# Waveshape_LFO_v1_Main.net
KiCad netlist of a schematic drawn in Altium Designer
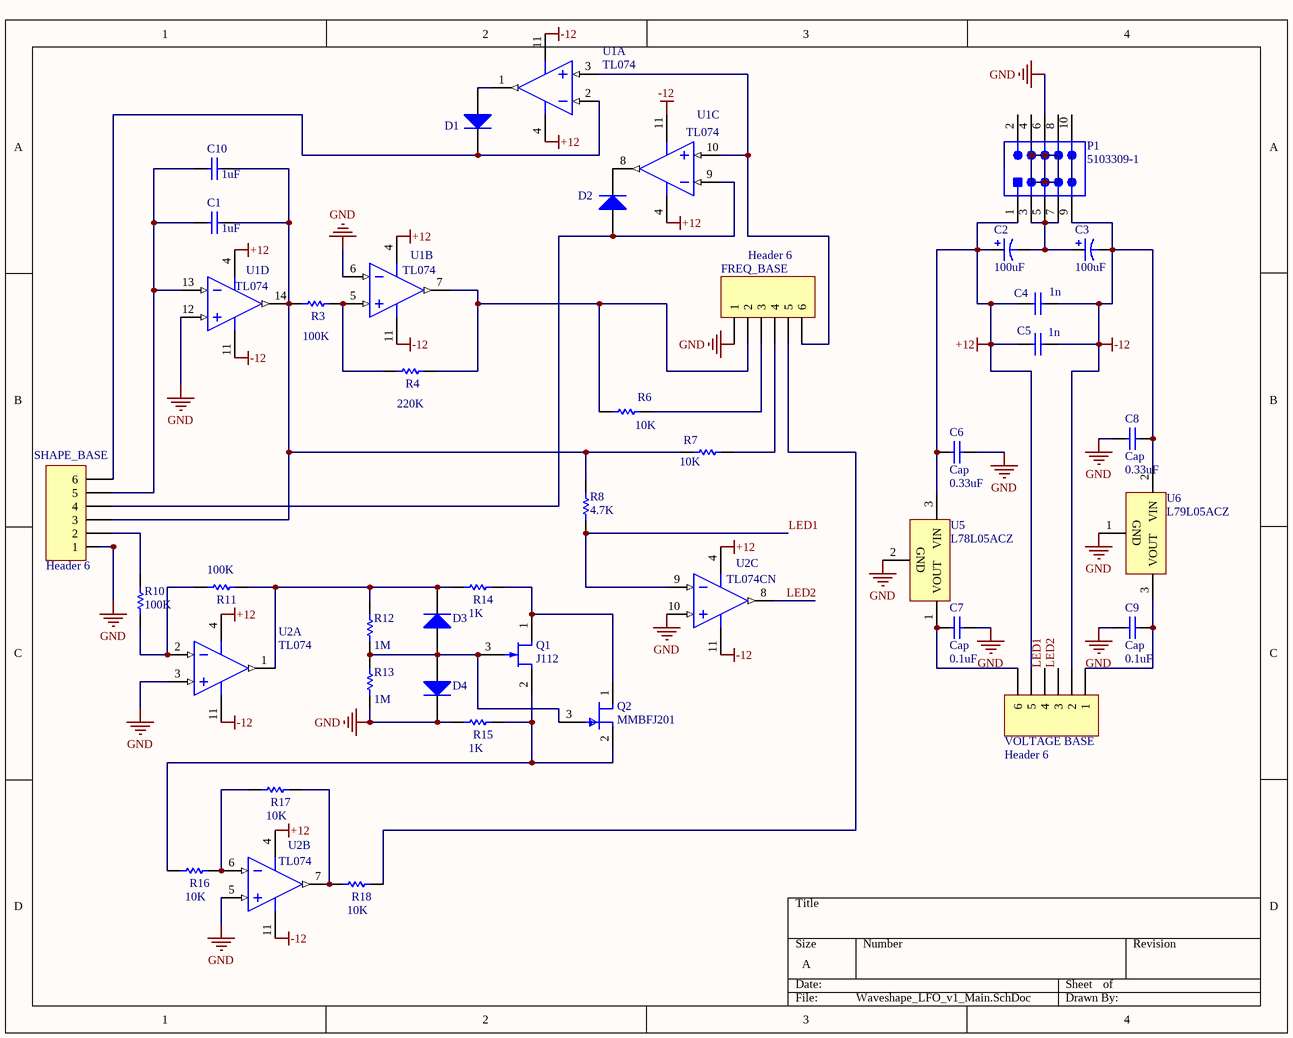
[diagram p0: Waveshape_LFO_v1_Main.SchDoc]

(export (version "E")
  (design (tool "Eeschema 10.0.6"))
  (components
    (comp (ref "C1")
      (value "1uF")
      (footprint "RAD-0.1")
      (description "Capacitor")
      (fields (field (name "Comment") "Cap") (field (name "PUBLISHER") "Altium Limited"))
      (libsource (lib "Miscellaneous Devices") (part "Cap"))
    )
    (comp (ref "C2")
      (value "100uF")
      (footprint "CAPR5-4X5")
      (description "Polarized Capacitor (Radial)")
      (fields (field (name "Comment") "Cap Pol1") (field (name "PUBLISHER") "Altium Limited"))
      (libsource (lib "Miscellaneous Devices") (part "Cap Pol1"))
    )
    (comp (ref "C3")
      (value "100uF")
      (footprint "CAPR5-4X5")
      (description "Polarized Capacitor (Radial)")
      (fields (field (name "Comment") "Cap Pol1") (field (name "PUBLISHER") "Altium Limited"))
      (libsource (lib "Miscellaneous Devices") (part "Cap Pol1"))
    )
    (comp (ref "C4")
      (value "1n")
      (footprint "RAD-0.1")
      (description "Capacitor")
      (fields (field (name "Comment") "Cap") (field (name "PUBLISHER") "Altium Limited"))
      (libsource (lib "Miscellaneous Devices") (part "Cap"))
    )
    (comp (ref "C5")
      (value "1n")
      (footprint "RAD-0.1")
      (description "Capacitor")
      (fields (field (name "Comment") "Cap") (field (name "PUBLISHER") "Altium Limited"))
      (libsource (lib "Miscellaneous Devices") (part "Cap"))
    )
    (comp (ref "C6")
      (value "Cap")
      (footprint "RAD-0.3")
      (description "Capacitor")
      (fields (field (name "ALTIUM_VALUE") "0.33uF") (field (name "PUBLISHER") "Altium Limited"))
      (libsource (lib "Miscellaneous Devices") (part "Cap"))
    )
    (comp (ref "C7")
      (value "Cap")
      (footprint "RAD-0.3")
      (description "Capacitor")
      (fields (field (name "ALTIUM_VALUE") "0.1uF") (field (name "PUBLISHER") "Altium Limited"))
      (libsource (lib "Miscellaneous Devices") (part "Cap"))
    )
    (comp (ref "C8")
      (value "Cap")
      (footprint "RAD-0.3")
      (description "Capacitor")
      (fields (field (name "ALTIUM_VALUE") "0.33uF") (field (name "PUBLISHER") "Altium Limited"))
      (libsource (lib "Miscellaneous Devices") (part "Cap"))
    )
    (comp (ref "C9")
      (value "Cap")
      (footprint "RAD-0.3")
      (description "Capacitor")
      (fields (field (name "ALTIUM_VALUE") "0.1uF") (field (name "PUBLISHER") "Altium Limited"))
      (libsource (lib "Miscellaneous Devices") (part "Cap"))
    )
    (comp (ref "C10")
      (value "1uF")
      (footprint "RAD-0.1")
      (description "Capacitor")
      (fields (field (name "Comment") "Cap") (field (name "PUBLISHER") "Altium Limited"))
      (libsource (lib "Miscellaneous Devices") (part "Cap"))
    )
    (comp (ref "D1")
      (value "Diode 1N4148")
      (footprint "DO-35")
      (description "High Conductance Fast Diode")
      (fields (field (name "PUBLISHER") "Altium Limited"))
      (libsource (lib "Miscellaneous Devices") (part "Diode 1N4148"))
    )
    (comp (ref "D2")
      (value "Diode 1N4148")
      (footprint "DO-35")
      (description "High Conductance Fast Diode")
      (fields (field (name "PUBLISHER") "Altium Limited"))
      (libsource (lib "Miscellaneous Devices") (part "Diode 1N4148"))
    )
    (comp (ref "D3")
      (value "1N4148")
      (footprint "DO-35")
      (description "High Conductance Fast Diode")
      (fields (field (name "PUBLISHER") "Altium Limited"))
      (libsource (lib "Miscellaneous Devices") (part "Diode 1N4148"))
    )
    (comp (ref "D4")
      (value "Diode 1N4148")
      (footprint "DO-35")
      (description "High Conductance Fast Diode")
      (fields (field (name "PUBLISHER") "Altium Limited"))
      (libsource (lib "Miscellaneous Devices") (part "Diode 1N4148"))
    )
    (comp (ref "FREQ_BASE")
      (value "Header 6")
      (footprint "HDR1X6")
      (description "Header, 6-Pin")
      (fields (field (name "PUBLISHER") "Altium Limited"))
      (libsource (lib "") (part "Header 6_1"))
    )
    (comp (ref "P1")
      (value "5103309-1")
      (footprint "TECO-5103309-1_V")
      (fields (field (name "MANUFACTURER") "TE Connectivity"))
      (libsource (lib "Altium Content Vault") (part "CN-2P-M-R10"))
    )
    (comp (ref "Q1")
      (value "J112")
      (footprint "ONSC-TO-92-3-29-11")
      (description "JFET Chopper Transistor, N-Channel - Depletion, 3-Pin TO-92, Bulk Box")
      (fields (field (name "MANUFACTURER") "On Semiconductor"))
      (libsource (lib "Altium Content Vault") (part "ONSC-JFET-D1S2G3-3-B"))
    )
    (comp (ref "Q2")
      (value "MMBFJ201")
      (footprint "FP-318BM-IPC_C")
      (description "JFET N-Channel 40V  350mW Surface Mount SOT-23-3")
      (fields (field (name "MANUFACTURER") "ON Semiconductor"))
      (libsource (lib "Altium Content Vault") (part "14398f7355be6f33287877db3ee21c7"))
    )
    (comp (ref "R3")
      (value "100K")
      (footprint "AXIAL-0.3")
      (description "Resistor")
      (fields (field (name "PUBLISHER") "Altium Limited"))
      (libsource (lib "Miscellaneous Devices") (part "Res1"))
    )
    (comp (ref "R4")
      (value "220K")
      (footprint "AXIAL-0.3")
      (description "Resistor")
      (fields (field (name "PUBLISHER") "Altium Limited"))
      (libsource (lib "Miscellaneous Devices") (part "Res1"))
    )
    (comp (ref "R6")
      (value "10K")
      (footprint "AXIAL-0.3")
      (description "Resistor")
      (fields (field (name "PUBLISHER") "Altium Limited"))
      (libsource (lib "Miscellaneous Devices") (part "Res1"))
    )
    (comp (ref "R7")
      (value "10K")
      (footprint "AXIAL-0.3")
      (description "Resistor")
      (fields (field (name "PUBLISHER") "Altium Limited"))
      (libsource (lib "Miscellaneous Devices") (part "Res1"))
    )
    (comp (ref "R8")
      (value "4.7K")
      (footprint "AXIAL-0.3")
      (description "Resistor")
      (fields (field (name "PUBLISHER") "Altium Limited"))
      (libsource (lib "Miscellaneous Devices") (part "Res1"))
    )
    (comp (ref "R10")
      (value "100K")
      (footprint "AXIAL-0.3")
      (description "Resistor")
      (fields (field (name "PUBLISHER") "Altium Limited"))
      (libsource (lib "Miscellaneous Devices") (part "Res1"))
    )
    (comp (ref "R11")
      (value "100K")
      (footprint "AXIAL-0.3")
      (description "Resistor")
      (fields (field (name "PUBLISHER") "Altium Limited"))
      (libsource (lib "Miscellaneous Devices") (part "Res1"))
    )
    (comp (ref "R12")
      (value "1M")
      (footprint "AXIAL-0.3")
      (description "Resistor")
      (fields (field (name "PUBLISHER") "Altium Limited"))
      (libsource (lib "Miscellaneous Devices") (part "Res1"))
    )
    (comp (ref "R13")
      (value "1M")
      (footprint "AXIAL-0.3")
      (description "Resistor")
      (fields (field (name "PUBLISHER") "Altium Limited"))
      (libsource (lib "Miscellaneous Devices") (part "Res1"))
    )
    (comp (ref "R14")
      (value "1K")
      (footprint "AXIAL-0.3")
      (description "Resistor")
      (fields (field (name "PUBLISHER") "Altium Limited"))
      (libsource (lib "Miscellaneous Devices") (part "Res1"))
    )
    (comp (ref "R15")
      (value "1K")
      (footprint "AXIAL-0.3")
      (description "Resistor")
      (fields (field (name "PUBLISHER") "Altium Limited"))
      (libsource (lib "Miscellaneous Devices") (part "Res1"))
    )
    (comp (ref "R16")
      (value "10K")
      (footprint "AXIAL-0.3")
      (description "Resistor")
      (fields (field (name "PUBLISHER") "Altium Limited"))
      (libsource (lib "Miscellaneous Devices") (part "Res1"))
    )
    (comp (ref "R17")
      (value "10K")
      (footprint "AXIAL-0.3")
      (description "Resistor")
      (fields (field (name "PUBLISHER") "Altium Limited"))
      (libsource (lib "Miscellaneous Devices") (part "Res1"))
    )
    (comp (ref "R18")
      (value "10K")
      (footprint "AXIAL-0.3")
      (description "Resistor")
      (fields (field (name "PUBLISHER") "Altium Limited"))
      (libsource (lib "Miscellaneous Devices") (part "Res1"))
    )
    (comp (ref "SHAPE_BASE")
      (value "Header 6")
      (footprint "HDR1X6")
      (description "Header, 6-Pin")
      (fields (field (name "PUBLISHER") "Altium Limited"))
      (libsource (lib "") (part "Header 6_2"))
    )
    (comp (ref "U1")
      (value "TL074")
      (footprint "N0014A")
      (fields (field (name "MANUFACTURER") "Texas Instruments") (field (name "PARTNUMBER") "TL074CN"))
      (libsource (lib "Altium Content Vault") (part "TI-TLXX4X_MC3403-X14"))
    )
    (comp (ref "U2")
      (value "TL074CN")
      (footprint "N0014A")
      (fields (field (name "MANUFACTURER") "Texas Instruments") (field (name "PARTNUMBER") "TL074CN"))
      (libsource (lib "Altium Content Vault") (part "TI-TLXX4X_MC3403-X14"))
    )
    (comp (ref "U5")
      (value "L78L05ACZ")
      (footprint "TO-92")
      (description "Positive Voltage Regulator, 5V, 3-Pin TO-92")
      (libsource (lib "Altium Content Vault") (part "PM-REG-7805-SIL3"))
    )
    (comp (ref "U6")
      (value "L79L05ACZ")
      (footprint "TO-92")
      (description "Negative Voltage Regulator, -5V, 3-Pin TO-92")
      (libsource (lib "Altium Content Vault") (part "PM-REG-7905-SIL3A"))
    )
    (comp (ref "VOLTAGE BASE")
      (value "Header 6")
      (footprint "HDR1X6")
      (description "Header, 6-Pin")
      (fields (field (name "PUBLISHER") "Altium Limited"))
      (libsource (lib "Miscellaneous Connectors") (part "Header 6"))
    )
  )
  (nets
    (net (code "1") (name "+12") (class "Default")
      (node (ref "C2") (pin "1") (pinfunction "1_1") (pintype "passive"))
      (node (ref "C4") (pin "1") (pinfunction "1_1") (pintype "passive"))
      (node (ref "C5") (pin "1") (pinfunction "1_1") (pintype "passive"))
      (node (ref "C6") (pin "1") (pinfunction "1_1") (pintype "passive"))
      (node (ref "P1") (pin "1") (pinfunction "1_1") (pintype "passive"))
      (node (ref "U1") (pin "4") (pinfunction "VCC+_4") (pintype "power_in"))
      (node (ref "U2") (pin "4") (pinfunction "VCC+_4") (pintype "power_in"))
      (node (ref "U5") (pin "3") (pinfunction "VIN_3") (pintype "power_in"))
      (node (ref "VOLTAGE BASE") (pin "5") (pinfunction "5_5") (pintype "passive"))
    )
    (net (code "2") (name "-12") (class "Default")
      (node (ref "C3") (pin "2") (pinfunction "2_2") (pintype "passive"))
      (node (ref "C4") (pin "2") (pinfunction "2_2") (pintype "passive"))
      (node (ref "C5") (pin "2") (pinfunction "2_2") (pintype "passive"))
      (node (ref "C8") (pin "2") (pinfunction "2_2") (pintype "passive"))
      (node (ref "P1") (pin "9") (pinfunction "9_9") (pintype "passive"))
      (node (ref "U1") (pin "11") (pinfunction "VCC-_11") (pintype "power_in"))
      (node (ref "U2") (pin "11") (pinfunction "VCC-_11") (pintype "power_in"))
      (node (ref "U6") (pin "2") (pinfunction "VIN_2") (pintype "power_in"))
      (node (ref "VOLTAGE BASE") (pin "2") (pinfunction "2_2") (pintype "passive"))
    )
    (net (code "3") (name "/LED1") (class "Default")
      (node (ref "R8") (pin "1") (pinfunction "1_1") (pintype "passive"))
      (node (ref "U2") (pin "9") (pinfunction "IN3-_9") (pintype "input"))
      (node (ref "VOLTAGE BASE") (pin "4") (pinfunction "4_4") (pintype "passive"))
    )
    (net (code "4") (name "/LED2") (class "Default")
      (node (ref "U2") (pin "8") (pinfunction "OUT3_8") (pintype "output"))
      (node (ref "VOLTAGE BASE") (pin "3") (pinfunction "3_3") (pintype "passive"))
    )
    (net (code "5") (name "GND") (class "Default")
      (node (ref "C6") (pin "2") (pinfunction "2_2") (pintype "passive"))
      (node (ref "C7") (pin "2") (pinfunction "2_2") (pintype "passive"))
      (node (ref "C8") (pin "1") (pinfunction "1_1") (pintype "passive"))
      (node (ref "C9") (pin "1") (pinfunction "1_1") (pintype "passive"))
      (node (ref "D4") (pin "2") (pinfunction "K_2") (pintype "passive"))
      (node (ref "FREQ_BASE") (pin "1") (pinfunction "1_1") (pintype "passive"))
      (node (ref "P1") (pin "6") (pinfunction "6_6") (pintype "passive"))
      (node (ref "R13") (pin "1") (pinfunction "1_1") (pintype "passive"))
      (node (ref "R15") (pin "1") (pinfunction "1_1") (pintype "passive"))
      (node (ref "SHAPE_BASE") (pin "1") (pinfunction "1_1") (pintype "passive"))
      (node (ref "U1") (pin "12") (pinfunction "IN4+_12") (pintype "input"))
      (node (ref "U1") (pin "6") (pinfunction "IN2-_6") (pintype "input"))
      (node (ref "U2") (pin "10") (pinfunction "IN3+_10") (pintype "input"))
      (node (ref "U2") (pin "3") (pinfunction "IN1+_3") (pintype "input"))
      (node (ref "U2") (pin "5") (pinfunction "IN2+_5") (pintype "input"))
      (node (ref "U5") (pin "2") (pinfunction "GND_2") (pintype "power_in"))
      (node (ref "U6") (pin "1") (pinfunction "GND_1") (pintype "power_in"))
    )
    (net (code "6") (name "Net-(C2-Pad2)") (class "Default")
      (node (ref "C2") (pin "2") (pinfunction "2_2") (pintype "passive"))
      (node (ref "C3") (pin "1") (pinfunction "1_1") (pintype "passive"))
      (node (ref "P1") (pin "3") (pinfunction "3_3") (pintype "passive"))
      (node (ref "P1") (pin "5") (pinfunction "5_5") (pintype "passive"))
      (node (ref "P1") (pin "7") (pinfunction "7_7") (pintype "passive"))
    )
    (net (code "7") (name "Net-(D1-A)") (class "Default")
      (node (ref "D1") (pin "1") (pinfunction "A_1") (pintype "passive"))
      (node (ref "U1") (pin "1") (pinfunction "OUT1_1") (pintype "output"))
    )
    (net (code "8") (name "Net-(D1-K)") (class "Default")
      (node (ref "D1") (pin "2") (pinfunction "K_2") (pintype "passive"))
      (node (ref "SHAPE_BASE") (pin "6") (pinfunction "6_6") (pintype "passive"))
      (node (ref "U1") (pin "2") (pinfunction "IN1-_2") (pintype "input"))
    )
    (net (code "9") (name "Net-(D2-A)") (class "Default")
      (node (ref "D2") (pin "1") (pinfunction "A_1") (pintype "passive"))
      (node (ref "SHAPE_BASE") (pin "4") (pinfunction "4_4") (pintype "passive"))
      (node (ref "U1") (pin "9") (pinfunction "IN3-_9") (pintype "input"))
    )
    (net (code "10") (name "Net-(D2-K)") (class "Default")
      (node (ref "D2") (pin "2") (pinfunction "K_2") (pintype "passive"))
      (node (ref "U1") (pin "8") (pinfunction "OUT3_8") (pintype "output"))
    )
    (net (code "11") (name "Net-(D3-A)") (class "Default")
      (node (ref "D3") (pin "1") (pinfunction "A_1") (pintype "passive"))
      (node (ref "D4") (pin "1") (pinfunction "A_1") (pintype "passive"))
      (node (ref "Q1") (pin "3") (pinfunction "G_3") (pintype "passive"))
      (node (ref "Q2") (pin "3") (pinfunction "G_3") (pintype "passive"))
      (node (ref "R12") (pin "1") (pinfunction "1_1") (pintype "passive"))
      (node (ref "R13") (pin "2") (pinfunction "2_2") (pintype "passive"))
    )
    (net (code "12") (name "Net-(D3-K)") (class "Default")
      (node (ref "D3") (pin "2") (pinfunction "K_2") (pintype "passive"))
      (node (ref "R11") (pin "2") (pinfunction "2_2") (pintype "passive"))
      (node (ref "R12") (pin "2") (pinfunction "2_2") (pintype "passive"))
      (node (ref "R14") (pin "1") (pinfunction "1_1") (pintype "passive"))
      (node (ref "U2") (pin "1") (pinfunction "OUT1_1") (pintype "output"))
    )
    (net (code "13") (name "Net-(FREQ_BASE-Pad3)") (class "Default")
      (node (ref "FREQ_BASE") (pin "3") (pinfunction "3_3") (pintype "passive"))
      (node (ref "R6") (pin "2") (pinfunction "2_2") (pintype "passive"))
    )
    (net (code "14") (name "Net-(FREQ_BASE-Pad4)") (class "Default")
      (node (ref "FREQ_BASE") (pin "4") (pinfunction "4_4") (pintype "passive"))
      (node (ref "R7") (pin "1") (pinfunction "1_1") (pintype "passive"))
    )
    (net (code "15") (name "Net-(FREQ_BASE-Pad5)") (class "Default")
      (node (ref "FREQ_BASE") (pin "5") (pinfunction "5_5") (pintype "passive"))
      (node (ref "R18") (pin "2") (pinfunction "2_2") (pintype "passive"))
    )
    (net (code "16") (name "Net-(Q1-D)") (class "Default")
      (node (ref "Q1") (pin "1") (pinfunction "D_1") (pintype "passive"))
      (node (ref "Q2") (pin "1") (pinfunction "D_1") (pintype "passive"))
      (node (ref "R14") (pin "2") (pinfunction "2_2") (pintype "passive"))
    )
    (net (code "17") (name "Net-(Q1-S)") (class "Default")
      (node (ref "Q1") (pin "2") (pinfunction "S_2") (pintype "passive"))
      (node (ref "Q2") (pin "2") (pinfunction "S_2") (pintype "passive"))
      (node (ref "R15") (pin "2") (pinfunction "2_2") (pintype "passive"))
      (node (ref "R16") (pin "1") (pinfunction "1_1") (pintype "passive"))
    )
    (net (code "18") (name "Net-(R10-Pad2)") (class "Default")
      (node (ref "R10") (pin "2") (pinfunction "2_2") (pintype "passive"))
      (node (ref "SHAPE_BASE") (pin "2") (pinfunction "2_2") (pintype "passive"))
    )
    (net (code "19") (name "Net-(U1A-IN1+)") (class "Default")
      (node (ref "FREQ_BASE") (pin "6") (pinfunction "6_6") (pintype "passive"))
      (node (ref "U1") (pin "10") (pinfunction "IN3+_10") (pintype "input"))
      (node (ref "U1") (pin "3") (pinfunction "IN1+_3") (pintype "input"))
    )
    (net (code "20") (name "Net-(U1B-IN2+)") (class "Default")
      (node (ref "R3") (pin "2") (pinfunction "2_2") (pintype "passive"))
      (node (ref "R4") (pin "1") (pinfunction "1_1") (pintype "passive"))
      (node (ref "U1") (pin "5") (pinfunction "IN2+_5") (pintype "input"))
    )
    (net (code "21") (name "Net-(U1B-OUT2)") (class "Default")
      (node (ref "FREQ_BASE") (pin "2") (pinfunction "2_2") (pintype "passive"))
      (node (ref "R4") (pin "2") (pinfunction "2_2") (pintype "passive"))
      (node (ref "R6") (pin "1") (pinfunction "1_1") (pintype "passive"))
      (node (ref "U1") (pin "7") (pinfunction "OUT2_7") (pintype "output"))
    )
    (net (code "22") (name "Net-(U1D-IN4-)") (class "Default")
      (node (ref "C1") (pin "1") (pinfunction "1_1") (pintype "passive"))
      (node (ref "C10") (pin "1") (pinfunction "1_1") (pintype "passive"))
      (node (ref "SHAPE_BASE") (pin "5") (pinfunction "5_5") (pintype "passive"))
      (node (ref "U1") (pin "13") (pinfunction "IN4-_13") (pintype "input"))
    )
    (net (code "23") (name "Net-(U1D-OUT4)") (class "Default")
      (node (ref "C1") (pin "2") (pinfunction "2_2") (pintype "passive"))
      (node (ref "C10") (pin "2") (pinfunction "2_2") (pintype "passive"))
      (node (ref "R3") (pin "1") (pinfunction "1_1") (pintype "passive"))
      (node (ref "R7") (pin "2") (pinfunction "2_2") (pintype "passive"))
      (node (ref "R8") (pin "2") (pinfunction "2_2") (pintype "passive"))
      (node (ref "SHAPE_BASE") (pin "3") (pinfunction "3_3") (pintype "passive"))
      (node (ref "U1") (pin "14") (pinfunction "OUT4_14") (pintype "output"))
    )
    (net (code "24") (name "Net-(U2A-IN1-)") (class "Default")
      (node (ref "R10") (pin "1") (pinfunction "1_1") (pintype "passive"))
      (node (ref "R11") (pin "1") (pinfunction "1_1") (pintype "passive"))
      (node (ref "U2") (pin "2") (pinfunction "IN1-_2") (pintype "input"))
    )
    (net (code "25") (name "Net-(U2B-IN2-)") (class "Default")
      (node (ref "R16") (pin "2") (pinfunction "2_2") (pintype "passive"))
      (node (ref "R17") (pin "1") (pinfunction "1_1") (pintype "passive"))
      (node (ref "U2") (pin "6") (pinfunction "IN2-_6") (pintype "input"))
    )
    (net (code "26") (name "Net-(U2B-OUT2)") (class "Default")
      (node (ref "R17") (pin "2") (pinfunction "2_2") (pintype "passive"))
      (node (ref "R18") (pin "1") (pinfunction "1_1") (pintype "passive"))
      (node (ref "U2") (pin "7") (pinfunction "OUT2_7") (pintype "output"))
    )
    (net (code "27") (name "Net-(U5-VOUT)") (class "Default")
      (node (ref "C7") (pin "1") (pinfunction "1_1") (pintype "passive"))
      (node (ref "U5") (pin "1") (pinfunction "VOUT_1") (pintype "power_in"))
      (node (ref "VOLTAGE BASE") (pin "6") (pinfunction "6_6") (pintype "passive"))
    )
    (net (code "28") (name "Net-(U6-VOUT)") (class "Default")
      (node (ref "C9") (pin "2") (pinfunction "2_2") (pintype "passive"))
      (node (ref "U6") (pin "3") (pinfunction "VOUT_3") (pintype "power_in"))
      (node (ref "VOLTAGE BASE") (pin "1") (pinfunction "1_1") (pintype "passive"))
    )
    (net (code "29") (name "unconnected-(P1-Pad2)") (class "Default")
      (node (ref "P1") (pin "2") (pinfunction "2_2") (pintype "passive"))
    )
    (net (code "30") (name "unconnected-(P1-Pad4)") (class "Default")
      (node (ref "P1") (pin "4") (pinfunction "4_4") (pintype "passive"))
    )
    (net (code "31") (name "unconnected-(P1-Pad8)") (class "Default")
      (node (ref "P1") (pin "8") (pinfunction "8_8") (pintype "passive"))
    )
    (net (code "32") (name "unconnected-(P1-Pad10)") (class "Default")
      (node (ref "P1") (pin "10") (pinfunction "10_10") (pintype "passive"))
    )
  )
)
